# Fonte12e5VCC.net
KiCad netlist of a schematic drawn in EAGLE
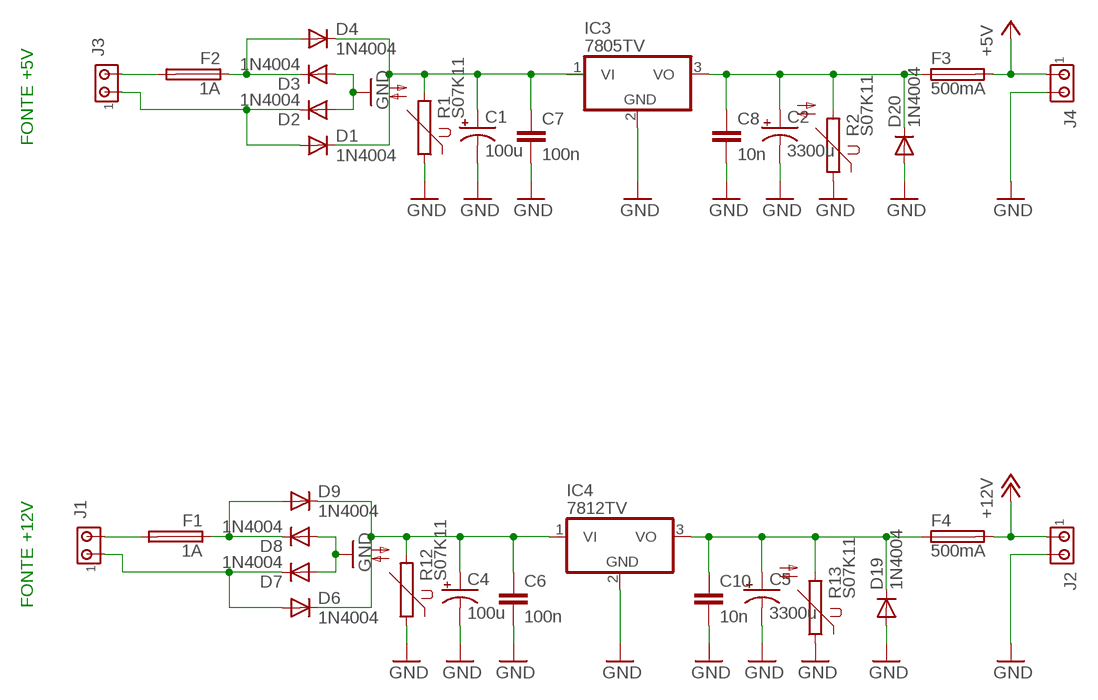
[diagram p0: schematic, sheet 1]

(export (version "E")
  (design (tool "Eeschema 10.0.6"))
  (components
    (comp (ref "C1")
      (value "100u")
      (footprint "eagle-import:E5-8,5")
      (libsource (lib "eagle-import") (part "CPOL-USE5-8.5"))
    )
    (comp (ref "C2")
      (value "3300u")
      (footprint "eagle-import:E5-8,5")
      (libsource (lib "eagle-import") (part "CPOL-USE5-8.5"))
    )
    (comp (ref "C4")
      (value "100u")
      (footprint "eagle-import:E5-8,5")
      (libsource (lib "eagle-import") (part "CPOL-USE5-8.5"))
    )
    (comp (ref "C5")
      (value "3300u")
      (footprint "eagle-import:E5-8,5")
      (libsource (lib "eagle-import") (part "CPOL-USE5-8.5"))
    )
    (comp (ref "C6")
      (value "100n")
      (footprint "eagle-import:C5B2.5")
      (libsource (lib "eagle-import") (part "C5/2.5"))
    )
    (comp (ref "C7")
      (value "100n")
      (footprint "eagle-import:C5B2.5")
      (libsource (lib "eagle-import") (part "C5/2.5"))
    )
    (comp (ref "C8")
      (value "10n")
      (footprint "eagle-import:C5B2.5")
      (libsource (lib "eagle-import") (part "C5/2.5"))
    )
    (comp (ref "C10")
      (value "10n")
      (footprint "eagle-import:C5B2.5")
      (libsource (lib "eagle-import") (part "C5/2.5"))
    )
    (comp (ref "D1")
      (value "1N4004")
      (footprint "eagle-import:DO41-10")
      (libsource (lib "eagle-import") (part "1N4004"))
    )
    (comp (ref "D2")
      (value "1N4004")
      (footprint "eagle-import:DO41-10")
      (libsource (lib "eagle-import") (part "1N4004"))
    )
    (comp (ref "D3")
      (value "1N4004")
      (footprint "eagle-import:DO41-10")
      (libsource (lib "eagle-import") (part "1N4004"))
    )
    (comp (ref "D4")
      (value "1N4004")
      (footprint "eagle-import:DO41-10")
      (libsource (lib "eagle-import") (part "1N4004"))
    )
    (comp (ref "D6")
      (value "1N4004")
      (footprint "eagle-import:DO41-10")
      (libsource (lib "eagle-import") (part "1N4004"))
    )
    (comp (ref "D7")
      (value "1N4004")
      (footprint "eagle-import:DO41-10")
      (libsource (lib "eagle-import") (part "1N4004"))
    )
    (comp (ref "D8")
      (value "1N4004")
      (footprint "eagle-import:DO41-10")
      (libsource (lib "eagle-import") (part "1N4004"))
    )
    (comp (ref "D9")
      (value "1N4004")
      (footprint "eagle-import:DO41-10")
      (libsource (lib "eagle-import") (part "1N4004"))
    )
    (comp (ref "D19")
      (value "1N4004")
      (footprint "eagle-import:DO41-10")
      (libsource (lib "eagle-import") (part "1N4004"))
    )
    (comp (ref "D20")
      (value "1N4004")
      (footprint "eagle-import:DO41-10")
      (libsource (lib "eagle-import") (part "1N4004"))
    )
    (comp (ref "F1")
      (value "1A")
      (footprint "eagle-import:GSH15")
      (fields (field (name "MPN") "64900001039"))
      (libsource (lib "eagle-import") (part "GSH15"))
    )
    (comp (ref "F2")
      (value "1A")
      (footprint "eagle-import:GSH15")
      (fields (field (name "MPN") "64900001039"))
      (libsource (lib "eagle-import") (part "GSH15"))
    )
    (comp (ref "F3")
      (value "500mA")
      (footprint "eagle-import:GSH15")
      (fields (field (name "MPN") "64900001039"))
      (libsource (lib "eagle-import") (part "GSH15"))
    )
    (comp (ref "F4")
      (value "500mA")
      (footprint "eagle-import:GSH15")
      (fields (field (name "MPN") "64900001039"))
      (libsource (lib "eagle-import") (part "GSH15"))
    )
    (comp (ref "IC3")
      (value "7805TV")
      (footprint "eagle-import:TO220V")
      (libsource (lib "eagle-import") (part "78TV05"))
    )
    (comp (ref "IC4")
      (value "7812TV")
      (footprint "eagle-import:TO220V")
      (libsource (lib "eagle-import") (part "78TV12"))
    )
    (comp (ref "J1")
      (value "MTA02-156")
      (footprint "eagle-import:1X2MTA")
      (libsource (lib "eagle-import") (part "MTA02-156"))
    )
    (comp (ref "J2")
      (value "MTA02-156")
      (footprint "eagle-import:1X2MTA")
      (libsource (lib "eagle-import") (part "MTA02-156"))
    )
    (comp (ref "J3")
      (value "MTA02-156")
      (footprint "eagle-import:1X2MTA")
      (libsource (lib "eagle-import") (part "MTA02-156"))
    )
    (comp (ref "J4")
      (value "MTA02-156")
      (footprint "eagle-import:1X2MTA")
      (libsource (lib "eagle-import") (part "MTA02-156"))
    )
    (comp (ref "R1")
      (value "S07K11")
      (footprint "eagle-import:S07K11")
      (libsource (lib "eagle-import") (part "S07K11"))
    )
    (comp (ref "R2")
      (value "S07K11")
      (footprint "eagle-import:S07K11")
      (libsource (lib "eagle-import") (part "S07K11"))
    )
    (comp (ref "R12")
      (value "S07K11")
      (footprint "eagle-import:S07K11")
      (libsource (lib "eagle-import") (part "S07K11"))
    )
    (comp (ref "R13")
      (value "S07K11")
      (footprint "eagle-import:S07K11")
      (libsource (lib "eagle-import") (part "S07K11"))
    )
  )
  (nets
    (net (code "1") (name "+5V") (class "Default")
      (node (ref "F3") (pin "2") (pinfunction "2_2") (pintype "passive"))
      (node (ref "J4") (pin "1") (pinfunction "1_1") (pintype "passive"))
    )
    (net (code "2") (name "+12V") (class "Default")
      (node (ref "F4") (pin "2") (pinfunction "2_2") (pintype "passive"))
      (node (ref "J2") (pin "1") (pinfunction "1_1") (pintype "passive"))
    )
    (net (code "3") (name "GND") (class "Default")
      (node (ref "C1") (pin "-") (pinfunction "-_-") (pintype "passive"))
      (node (ref "C10") (pin "2") (pinfunction "2_2") (pintype "passive"))
      (node (ref "C2") (pin "-") (pinfunction "-_-") (pintype "passive"))
      (node (ref "C4") (pin "-") (pinfunction "-_-") (pintype "passive"))
      (node (ref "C5") (pin "-") (pinfunction "-_-") (pintype "passive"))
      (node (ref "C6") (pin "2") (pinfunction "2_2") (pintype "passive"))
      (node (ref "C7") (pin "2") (pinfunction "2_2") (pintype "passive"))
      (node (ref "C8") (pin "2") (pinfunction "2_2") (pintype "passive"))
      (node (ref "D19") (pin "A") (pinfunction "A_A") (pintype "passive"))
      (node (ref "D2") (pin "A") (pinfunction "A_A") (pintype "passive"))
      (node (ref "D20") (pin "A") (pinfunction "A_A") (pintype "passive"))
      (node (ref "D3") (pin "A") (pinfunction "A_A") (pintype "passive"))
      (node (ref "D7") (pin "A") (pinfunction "A_A") (pintype "passive"))
      (node (ref "D8") (pin "A") (pinfunction "A_A") (pintype "passive"))
      (node (ref "IC3") (pin "2") (pinfunction "GND_2") (pintype "passive"))
      (node (ref "IC4") (pin "2") (pinfunction "GND_2") (pintype "passive"))
      (node (ref "J2") (pin "2") (pinfunction "2_2") (pintype "passive"))
      (node (ref "J4") (pin "2") (pinfunction "2_2") (pintype "passive"))
      (node (ref "R1") (pin "1") (pinfunction "1_1") (pintype "passive"))
      (node (ref "R12") (pin "1") (pinfunction "1_1") (pintype "passive"))
      (node (ref "R13") (pin "1") (pinfunction "1_1") (pintype "passive"))
      (node (ref "R2") (pin "1") (pinfunction "1_1") (pintype "passive"))
    )
    (net (code "4") (name "Net-(D1-PadA)") (class "Default")
      (node (ref "D1") (pin "A") (pinfunction "A_A") (pintype "passive"))
      (node (ref "D2") (pin "C") (pinfunction "C_C") (pintype "passive"))
      (node (ref "J3") (pin "1") (pinfunction "1_1") (pintype "passive"))
    )
    (net (code "5") (name "Net-(D3-PadC)") (class "Default")
      (node (ref "D3") (pin "C") (pinfunction "C_C") (pintype "passive"))
      (node (ref "D4") (pin "A") (pinfunction "A_A") (pintype "passive"))
      (node (ref "F2") (pin "1") (pinfunction "1_1") (pintype "passive"))
    )
    (net (code "6") (name "Net-(D6-PadA)") (class "Default")
      (node (ref "D6") (pin "A") (pinfunction "A_A") (pintype "passive"))
      (node (ref "D7") (pin "C") (pinfunction "C_C") (pintype "passive"))
      (node (ref "J1") (pin "1") (pinfunction "1_1") (pintype "passive"))
    )
    (net (code "7") (name "Net-(D8-PadC)") (class "Default")
      (node (ref "D8") (pin "C") (pinfunction "C_C") (pintype "passive"))
      (node (ref "D9") (pin "A") (pinfunction "A_A") (pintype "passive"))
      (node (ref "F1") (pin "1") (pinfunction "1_1") (pintype "passive"))
    )
    (net (code "8") (name "Net-(F1-Pad2)") (class "Default")
      (node (ref "F1") (pin "2") (pinfunction "2_2") (pintype "passive"))
      (node (ref "J1") (pin "2") (pinfunction "2_2") (pintype "passive"))
    )
    (net (code "9") (name "Net-(F2-Pad2)") (class "Default")
      (node (ref "F2") (pin "2") (pinfunction "2_2") (pintype "passive"))
      (node (ref "J3") (pin "2") (pinfunction "2_2") (pintype "passive"))
    )
    (net (code "10") (name "Net-(IC3-VI)") (class "Default")
      (node (ref "C1") (pin "+") (pinfunction "+_+") (pintype "passive"))
      (node (ref "C7") (pin "1") (pinfunction "1_1") (pintype "passive"))
      (node (ref "D1") (pin "C") (pinfunction "C_C") (pintype "passive"))
      (node (ref "D4") (pin "C") (pinfunction "C_C") (pintype "passive"))
      (node (ref "IC3") (pin "1") (pinfunction "VI_1") (pintype "input"))
      (node (ref "R1") (pin "2") (pinfunction "2_2") (pintype "passive"))
    )
    (net (code "11") (name "Net-(IC3-VO)") (class "Default")
      (node (ref "C2") (pin "+") (pinfunction "+_+") (pintype "passive"))
      (node (ref "C8") (pin "1") (pinfunction "1_1") (pintype "passive"))
      (node (ref "D20") (pin "C") (pinfunction "C_C") (pintype "passive"))
      (node (ref "F3") (pin "1") (pinfunction "1_1") (pintype "passive"))
      (node (ref "IC3") (pin "3") (pinfunction "VO_3") (pintype "passive"))
      (node (ref "R2") (pin "2") (pinfunction "2_2") (pintype "passive"))
    )
    (net (code "12") (name "Net-(IC4-VI)") (class "Default")
      (node (ref "C4") (pin "+") (pinfunction "+_+") (pintype "passive"))
      (node (ref "C6") (pin "1") (pinfunction "1_1") (pintype "passive"))
      (node (ref "D6") (pin "C") (pinfunction "C_C") (pintype "passive"))
      (node (ref "D9") (pin "C") (pinfunction "C_C") (pintype "passive"))
      (node (ref "IC4") (pin "1") (pinfunction "VI_1") (pintype "input"))
      (node (ref "R12") (pin "2") (pinfunction "2_2") (pintype "passive"))
    )
    (net (code "13") (name "Net-(IC4-VO)") (class "Default")
      (node (ref "C10") (pin "1") (pinfunction "1_1") (pintype "passive"))
      (node (ref "C5") (pin "+") (pinfunction "+_+") (pintype "passive"))
      (node (ref "D19") (pin "C") (pinfunction "C_C") (pintype "passive"))
      (node (ref "F4") (pin "1") (pinfunction "1_1") (pintype "passive"))
      (node (ref "IC4") (pin "3") (pinfunction "VO_3") (pintype "passive"))
      (node (ref "R13") (pin "2") (pinfunction "2_2") (pintype "passive"))
    )
  )
)
